# 1_P1.net
KiCad netlist of a schematic drawn in Altium Designer
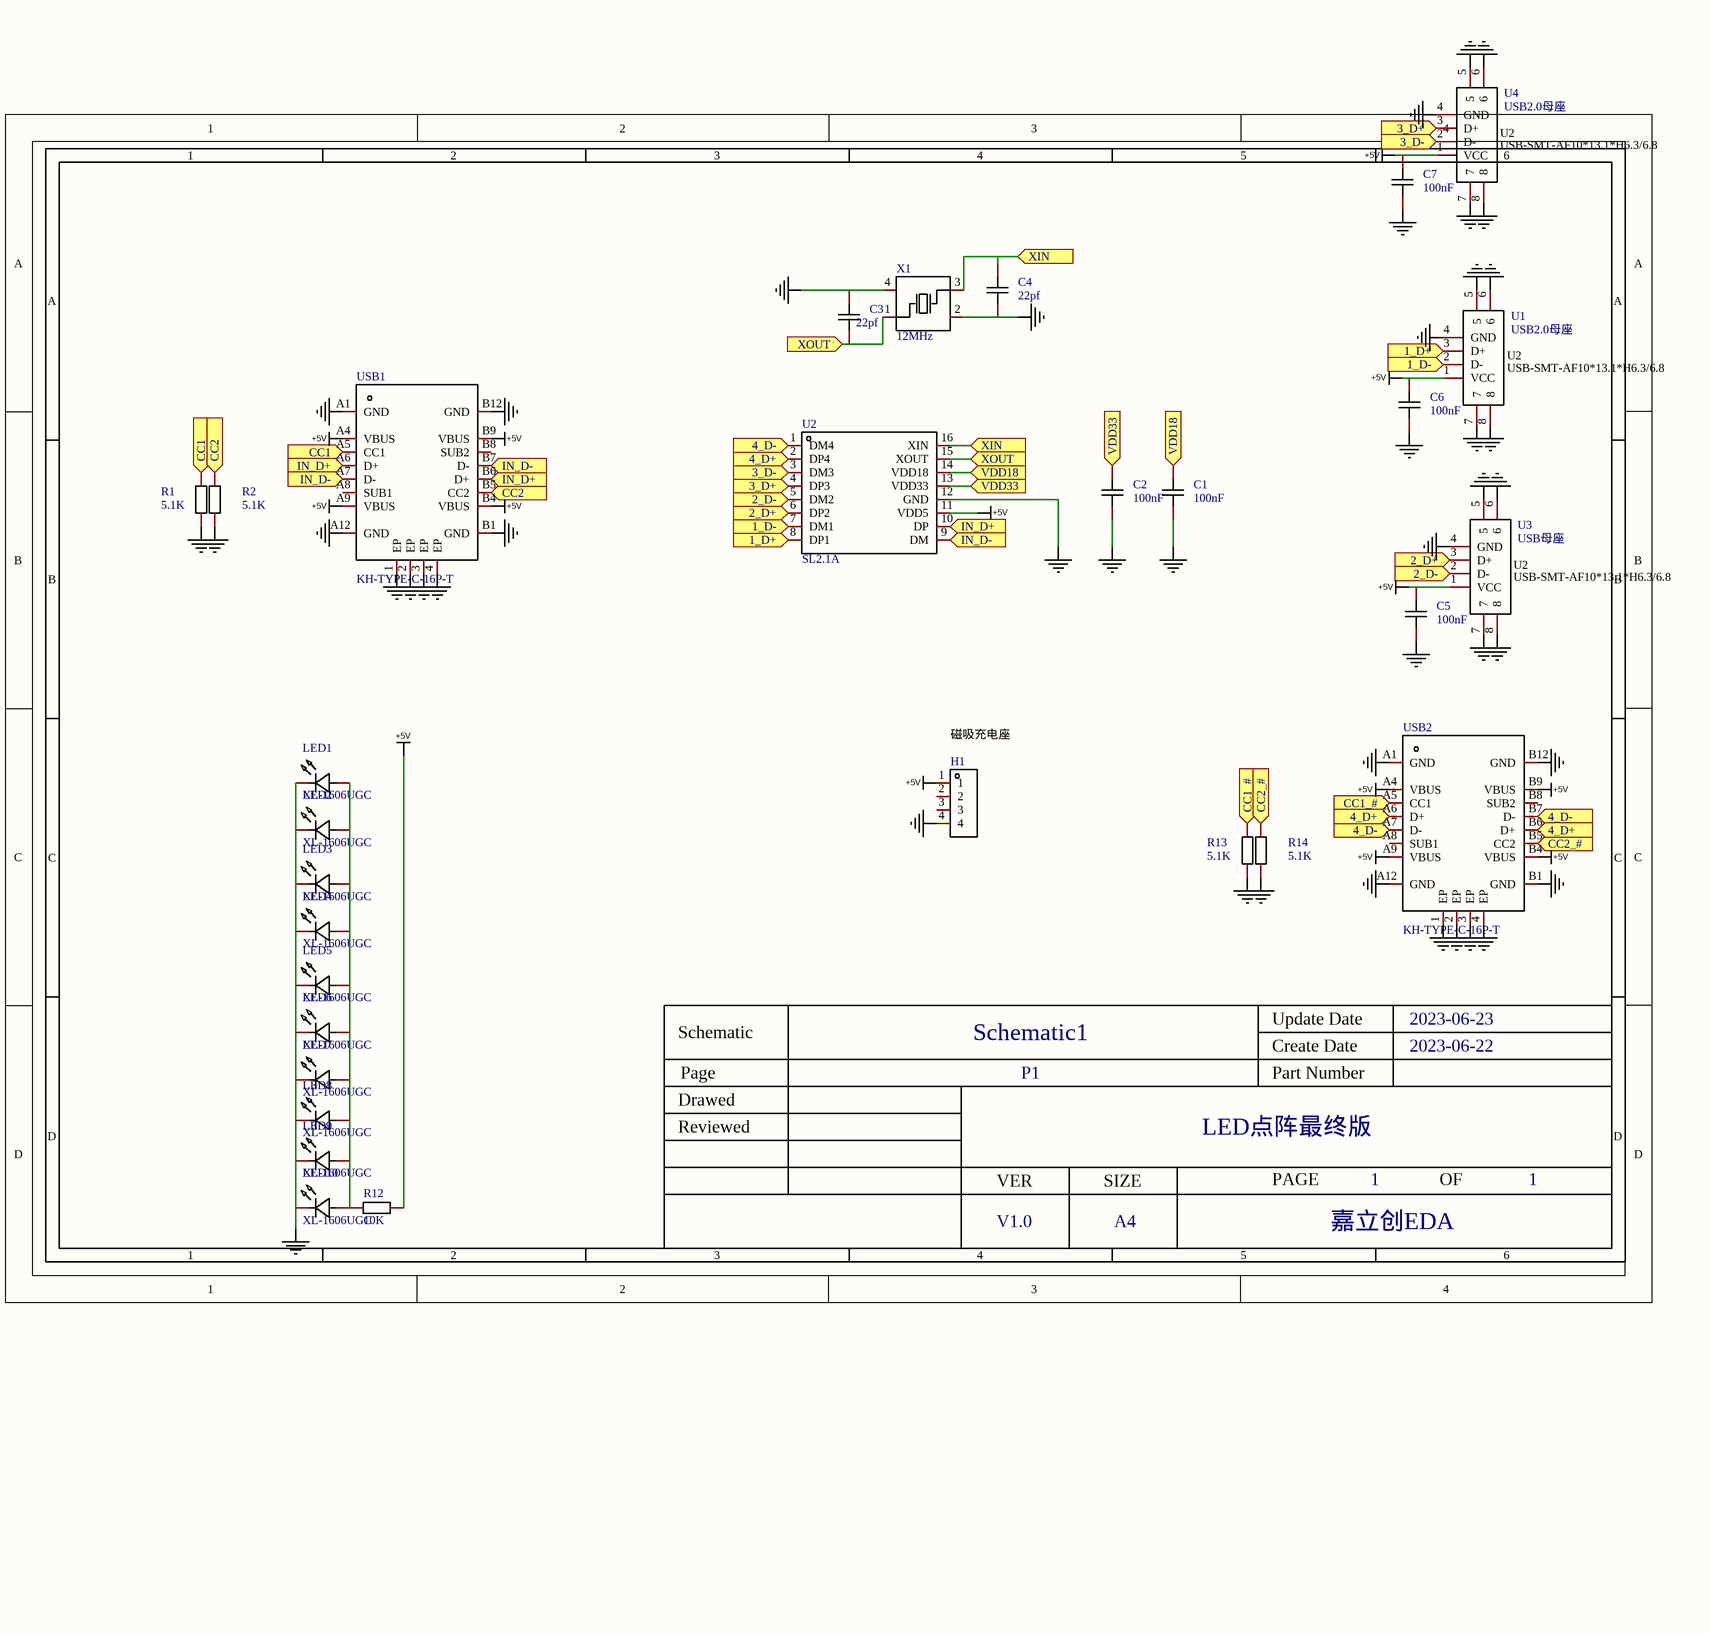
[diagram p0: 1_P1.schdoc]

(export (version "E")
  (design (tool "Eeschema 10.0.6"))
  (components
    (comp (ref "C1")
      (value "100nF")
      (fields (field (name "NAME") "100nF"))
      (libsource (lib "altium-import") (part "root_3_CAP_0603_"))
    )
    (comp (ref "C2")
      (value "100nF")
      (fields (field (name "NAME") "100nF"))
      (libsource (lib "altium-import") (part "root_3_CAP_0603_"))
    )
    (comp (ref "C3")
      (value "22pf")
      (fields (field (name "NAME") "22pf"))
      (libsource (lib "altium-import") (part "root_1_CAP_0603_"))
    )
    (comp (ref "C4")
      (value "22pf")
      (fields (field (name "NAME") "22pf"))
      (libsource (lib "altium-import") (part "root_1_CAP_0603_"))
    )
    (comp (ref "C5")
      (value "100nF")
      (fields (field (name "NAME") "100nF"))
      (libsource (lib "altium-import") (part "root_1_CAP_0603_"))
    )
    (comp (ref "C6")
      (value "100nF")
      (fields (field (name "NAME") "100nF"))
      (libsource (lib "altium-import") (part "root_1_CAP_0603_"))
    )
    (comp (ref "C7")
      (value "100nF")
      (fields (field (name "NAME") "100nF"))
      (libsource (lib "altium-import") (part "root_1_CAP_0603_"))
    )
    (comp (ref "H1")
      (value "HDR-M_2.54_1x4P")
      (libsource (lib "altium-import") (part "root_0_HDR-M_2.54_1x4P_"))
    )
    (comp (ref "LED1")
      (value "XL-1606UGC")
      (description "发光颜色:翠绿;主波长:520nm~530nm;色温:-;功率:80mW;安装方式:侧贴;")
      (fields (field (name "NAME") "XL-1606UGC") (field (name "MANUFACTURER") "XINGLIGHT(成兴光)"))
      (libsource (lib "altium-import") (part "root_0_XL-1606UGC_"))
    )
    (comp (ref "LED2")
      (value "XL-1606UGC")
      (description "发光颜色:翠绿;主波长:520nm~530nm;色温:-;功率:80mW;安装方式:侧贴;")
      (fields (field (name "NAME") "XL-1606UGC") (field (name "MANUFACTURER") "XINGLIGHT(成兴光)"))
      (libsource (lib "altium-import") (part "root_0_XL-1606UGC_"))
    )
    (comp (ref "LED3")
      (value "XL-1606UGC")
      (description "发光颜色:翠绿;主波长:520nm~530nm;色温:-;功率:80mW;安装方式:侧贴;")
      (fields (field (name "NAME") "XL-1606UGC") (field (name "MANUFACTURER") "XINGLIGHT(成兴光)"))
      (libsource (lib "altium-import") (part "root_0_XL-1606UGC_"))
    )
    (comp (ref "LED4")
      (value "XL-1606UGC")
      (description "发光颜色:翠绿;主波长:520nm~530nm;色温:-;功率:80mW;安装方式:侧贴;")
      (fields (field (name "NAME") "XL-1606UGC") (field (name "MANUFACTURER") "XINGLIGHT(成兴光)"))
      (libsource (lib "altium-import") (part "root_0_XL-1606UGC_"))
    )
    (comp (ref "LED5")
      (value "XL-1606UGC")
      (description "发光颜色:翠绿;主波长:520nm~530nm;色温:-;功率:80mW;安装方式:侧贴;")
      (fields (field (name "NAME") "XL-1606UGC") (field (name "MANUFACTURER") "XINGLIGHT(成兴光)"))
      (libsource (lib "altium-import") (part "root_0_XL-1606UGC_"))
    )
    (comp (ref "LED6")
      (value "XL-1606UGC")
      (description "发光颜色:翠绿;主波长:520nm~530nm;色温:-;功率:80mW;安装方式:侧贴;")
      (fields (field (name "NAME") "XL-1606UGC") (field (name "MANUFACTURER") "XINGLIGHT(成兴光)"))
      (libsource (lib "altium-import") (part "root_0_XL-1606UGC_"))
    )
    (comp (ref "LED7")
      (value "XL-1606UGC")
      (description "发光颜色:翠绿;主波长:520nm~530nm;色温:-;功率:80mW;安装方式:侧贴;")
      (fields (field (name "NAME") "XL-1606UGC") (field (name "MANUFACTURER") "XINGLIGHT(成兴光)"))
      (libsource (lib "altium-import") (part "root_0_XL-1606UGC_"))
    )
    (comp (ref "LED8")
      (value "XL-1606UGC")
      (description "发光颜色:翠绿;主波长:520nm~530nm;色温:-;功率:80mW;安装方式:侧贴;")
      (fields (field (name "NAME") "XL-1606UGC") (field (name "MANUFACTURER") "XINGLIGHT(成兴光)"))
      (libsource (lib "altium-import") (part "root_0_XL-1606UGC_"))
    )
    (comp (ref "LED9")
      (value "XL-1606UGC")
      (description "发光颜色:翠绿;主波长:520nm~530nm;色温:-;功率:80mW;安装方式:侧贴;")
      (fields (field (name "NAME") "XL-1606UGC") (field (name "MANUFACTURER") "XINGLIGHT(成兴光)"))
      (libsource (lib "altium-import") (part "root_0_XL-1606UGC_"))
    )
    (comp (ref "LED10")
      (value "XL-1606UGC")
      (description "发光颜色:翠绿;主波长:520nm~530nm;色温:-;功率:80mW;安装方式:侧贴;")
      (fields (field (name "NAME") "XL-1606UGC") (field (name "MANUFACTURER") "XINGLIGHT(成兴光)"))
      (libsource (lib "altium-import") (part "root_0_XL-1606UGC_"))
    )
    (comp (ref "R1")
      (value "5.1K")
      (fields (field (name "NAME") "5.1K"))
      (libsource (lib "altium-import") (part "root_1_Res_0603_"))
    )
    (comp (ref "R2")
      (value "5.1K")
      (fields (field (name "NAME") "5.1K"))
      (libsource (lib "altium-import") (part "root_1_Res_0603_"))
    )
    (comp (ref "R12")
      (value "10K")
      (fields (field (name "NAME") "10K"))
      (libsource (lib "altium-import") (part "root_0_Res_0603_"))
    )
    (comp (ref "R13")
      (value "5.1K")
      (fields (field (name "NAME") "5.1K"))
      (libsource (lib "altium-import") (part "root_1_Res_0603_"))
    )
    (comp (ref "R14")
      (value "5.1K")
      (fields (field (name "NAME") "5.1K"))
      (libsource (lib "altium-import") (part "root_1_Res_0603_"))
    )
    (comp (ref "U1")
      (value "USB-SMT-AF10.0-13.1*6.8/6.3")
      (fields (field (name "NAME") "USB2.0母座"))
      (libsource (lib "altium-import") (part "root_0_USB-SMT-AF10.0-13.1*6.8/6.3_"))
    )
    (comp (ref "U2")
      (value "SL2.1A")
      (description "应用功能:集线器;接口协议:-;")
      (fields (field (name "NAME") "SL2.1A") (field (name "MANUFACTURER") "CoreChips(和芯润德)"))
      (libsource (lib "altium-import") (part "root_0_SL2.1A_"))
    )
    (comp (ref "U3")
      (value "USB母座")
      (fields (field (name "NAME") "USB母座"))
      (libsource (lib "altium-import") (part "root_0_USB-SMT-AF10.0-13.1*6.8/6.3_"))
    )
    (comp (ref "U4")
      (value "USB-SMT-AF10.0-13.1*6.8/6.3")
      (fields (field (name "NAME") "USB2.0母座"))
      (libsource (lib "altium-import") (part "root_0_USB-SMT-AF10.0-13.1*6.8/6.3_"))
    )
    (comp (ref "USB1")
      (value "KH-TYPE-C-16P-T")
      (description "连接器类型:Type-C;标准:-;公母:母座;触点数量:16;端口数量:1;安装方式:卧贴;额定电流 - 电源:500mA;工作温度范围:-30℃~+80℃;")
      (fields (field (name "NAME") "KH-TYPE-C-16P-T") (field (name "MANUFACTURER") "kinghelm(金航标)"))
      (libsource (lib "altium-import") (part "root_0_KH-TYPE-C-16P-T_"))
    )
    (comp (ref "USB2")
      (value "KH-TYPE-C-16P-T")
      (description "连接器类型:Type-C;标准:-;公母:母座;触点数量:16;端口数量:1;安装方式:卧贴;额定电流 - 电源:500mA;工作温度范围:-30℃~+80℃;")
      (fields (field (name "NAME") "KH-TYPE-C-16P-T") (field (name "MANUFACTURER") "kinghelm(金航标)"))
      (libsource (lib "altium-import") (part "root_0_KH-TYPE-C-16P-T_"))
    )
    (comp (ref "X1")
      (value "12MHz")
      (description "频率:12MHz;频率公差:±10ppm;负载电容:20pF;")
      (fields
        (field (name "NAME") "12MHz")
        (field (name "MANUFACTURER") "YXC(扬兴晶振)")
        (field (name "MANUFACTURER PART") "X322512MSB4SI")
      )
      (libsource (lib "altium-import") (part "root_0_X322512MSB4SI_"))
    )
  )
  (nets
    (net (code "1") (name "+5V") (class "Default")
      (node (ref "C5") (pin "2") (pinfunction "2_2") (pintype "passive"))
      (node (ref "C6") (pin "2") (pinfunction "2_2") (pintype "passive"))
      (node (ref "C7") (pin "2") (pinfunction "2_2") (pintype "passive"))
      (node (ref "H1") (pin "1") (pinfunction "1_1") (pintype "passive"))
      (node (ref "R12") (pin "2") (pinfunction "2_2") (pintype "passive"))
      (node (ref "U1") (pin "1") (pinfunction "VCC_1") (pintype "passive"))
      (node (ref "U2") (pin "11") (pinfunction "VDD5_11") (pintype "passive"))
      (node (ref "U3") (pin "1") (pinfunction "VCC_1") (pintype "passive"))
      (node (ref "U4") (pin "1") (pinfunction "VCC_1") (pintype "passive"))
      (node (ref "USB1") (pin "A4") (pinfunction "VBUS_A4") (pintype "passive"))
      (node (ref "USB1") (pin "A9") (pinfunction "VBUS_A9") (pintype "passive"))
      (node (ref "USB1") (pin "B4") (pinfunction "VBUS_B4") (pintype "passive"))
      (node (ref "USB1") (pin "B9") (pinfunction "VBUS_B9") (pintype "passive"))
      (node (ref "USB2") (pin "A4") (pinfunction "VBUS_A4") (pintype "passive"))
      (node (ref "USB2") (pin "A9") (pinfunction "VBUS_A9") (pintype "passive"))
      (node (ref "USB2") (pin "B4") (pinfunction "VBUS_B4") (pintype "passive"))
      (node (ref "USB2") (pin "B9") (pinfunction "VBUS_B9") (pintype "passive"))
    )
    (net (code "2") (name "/1_D+") (class "Default")
      (node (ref "U1") (pin "3") (pinfunction "D+_3") (pintype "passive"))
      (node (ref "U2") (pin "8") (pinfunction "DP1_8") (pintype "passive"))
    )
    (net (code "3") (name "/1_D-") (class "Default")
      (node (ref "U1") (pin "2") (pinfunction "D-_2") (pintype "passive"))
      (node (ref "U2") (pin "7") (pinfunction "DM1_7") (pintype "passive"))
    )
    (net (code "4") (name "/2_D+") (class "Default")
      (node (ref "U2") (pin "6") (pinfunction "DP2_6") (pintype "passive"))
      (node (ref "U3") (pin "3") (pinfunction "D+_3") (pintype "passive"))
    )
    (net (code "5") (name "/2_D-") (class "Default")
      (node (ref "U2") (pin "5") (pinfunction "DM2_5") (pintype "passive"))
      (node (ref "U3") (pin "2") (pinfunction "D-_2") (pintype "passive"))
    )
    (net (code "6") (name "/3_D+") (class "Default")
      (node (ref "U2") (pin "4") (pinfunction "DP3_4") (pintype "passive"))
      (node (ref "U4") (pin "3") (pinfunction "D+_3") (pintype "passive"))
    )
    (net (code "7") (name "/3_D-") (class "Default")
      (node (ref "U2") (pin "3") (pinfunction "DM3_3") (pintype "passive"))
      (node (ref "U4") (pin "2") (pinfunction "D-_2") (pintype "passive"))
    )
    (net (code "8") (name "/4_D+") (class "Default")
      (node (ref "U2") (pin "2") (pinfunction "DP4_2") (pintype "passive"))
      (node (ref "USB2") (pin "A6") (pinfunction "D+_A6") (pintype "passive"))
      (node (ref "USB2") (pin "B6") (pinfunction "D+_B6") (pintype "passive"))
    )
    (net (code "9") (name "/4_D-") (class "Default")
      (node (ref "U2") (pin "1") (pinfunction "DM4_1") (pintype "passive"))
      (node (ref "USB2") (pin "A7") (pinfunction "D-_A7") (pintype "passive"))
      (node (ref "USB2") (pin "B7") (pinfunction "D-_B7") (pintype "passive"))
    )
    (net (code "10") (name "/CC1") (class "Default")
      (node (ref "R1") (pin "2") (pinfunction "2_2") (pintype "passive"))
      (node (ref "USB1") (pin "A5") (pinfunction "CC1_A5") (pintype "passive"))
    )
    (net (code "11") (name "/CC1_#") (class "Default")
      (node (ref "R13") (pin "2") (pinfunction "2_2") (pintype "passive"))
      (node (ref "USB2") (pin "A5") (pinfunction "CC1_A5") (pintype "passive"))
    )
    (net (code "12") (name "/CC2") (class "Default")
      (node (ref "R2") (pin "2") (pinfunction "2_2") (pintype "passive"))
      (node (ref "USB1") (pin "B5") (pinfunction "CC2_B5") (pintype "passive"))
    )
    (net (code "13") (name "/CC2_#") (class "Default")
      (node (ref "R14") (pin "2") (pinfunction "2_2") (pintype "passive"))
      (node (ref "USB2") (pin "B5") (pinfunction "CC2_B5") (pintype "passive"))
    )
    (net (code "14") (name "/IN_D+") (class "Default")
      (node (ref "U2") (pin "10") (pinfunction "DP_10") (pintype "passive"))
      (node (ref "USB1") (pin "A6") (pinfunction "D+_A6") (pintype "passive"))
      (node (ref "USB1") (pin "B6") (pinfunction "D+_B6") (pintype "passive"))
    )
    (net (code "15") (name "/IN_D-") (class "Default")
      (node (ref "U2") (pin "9") (pinfunction "DM_9") (pintype "passive"))
      (node (ref "USB1") (pin "A7") (pinfunction "D-_A7") (pintype "passive"))
      (node (ref "USB1") (pin "B7") (pinfunction "D-_B7") (pintype "passive"))
    )
    (net (code "16") (name "/VDD18") (class "Default")
      (node (ref "C1") (pin "1") (pinfunction "1_1") (pintype "passive"))
      (node (ref "U2") (pin "14") (pinfunction "VDD18_14") (pintype "passive"))
    )
    (net (code "17") (name "/VDD33") (class "Default")
      (node (ref "C2") (pin "1") (pinfunction "1_1") (pintype "passive"))
      (node (ref "U2") (pin "13") (pinfunction "VDD33_13") (pintype "passive"))
    )
    (net (code "18") (name "/XIN") (class "Default")
      (node (ref "C4") (pin "2") (pinfunction "2_2") (pintype "passive"))
      (node (ref "U2") (pin "16") (pinfunction "XIN_16") (pintype "passive"))
      (node (ref "X1") (pin "3") (pinfunction "OSC2_3") (pintype "passive"))
    )
    (net (code "19") (name "/XOUT") (class "Default")
      (node (ref "C3") (pin "1") (pinfunction "1_1") (pintype "passive"))
      (node (ref "U2") (pin "15") (pinfunction "XOUT_15") (pintype "passive"))
      (node (ref "X1") (pin "1") (pinfunction "OSC1_1") (pintype "passive"))
    )
    (net (code "20") (name "<NO NET>") (class "Default")
      (node (ref "C1") (pin "2") (pinfunction "2_2") (pintype "passive"))
      (node (ref "C2") (pin "2") (pinfunction "2_2") (pintype "passive"))
      (node (ref "C3") (pin "2") (pinfunction "2_2") (pintype "passive"))
      (node (ref "C4") (pin "1") (pinfunction "1_1") (pintype "passive"))
      (node (ref "C5") (pin "1") (pinfunction "1_1") (pintype "passive"))
      (node (ref "C6") (pin "1") (pinfunction "1_1") (pintype "passive"))
      (node (ref "C7") (pin "1") (pinfunction "1_1") (pintype "passive"))
      (node (ref "H1") (pin "4") (pinfunction "4_4") (pintype "passive"))
      (node (ref "LED1") (pin "2") (pinfunction "K_2") (pintype "passive"))
      (node (ref "LED10") (pin "2") (pinfunction "K_2") (pintype "passive"))
      (node (ref "LED2") (pin "2") (pinfunction "K_2") (pintype "passive"))
      (node (ref "LED3") (pin "2") (pinfunction "K_2") (pintype "passive"))
      (node (ref "LED4") (pin "2") (pinfunction "K_2") (pintype "passive"))
      (node (ref "LED5") (pin "2") (pinfunction "K_2") (pintype "passive"))
      (node (ref "LED6") (pin "2") (pinfunction "K_2") (pintype "passive"))
      (node (ref "LED7") (pin "2") (pinfunction "K_2") (pintype "passive"))
      (node (ref "LED8") (pin "2") (pinfunction "K_2") (pintype "passive"))
      (node (ref "LED9") (pin "2") (pinfunction "K_2") (pintype "passive"))
      (node (ref "R1") (pin "1") (pinfunction "1_1") (pintype "passive"))
      (node (ref "R13") (pin "1") (pinfunction "1_1") (pintype "passive"))
      (node (ref "R14") (pin "1") (pinfunction "1_1") (pintype "passive"))
      (node (ref "R2") (pin "1") (pinfunction "1_1") (pintype "passive"))
      (node (ref "U1") (pin "4") (pinfunction "GND_4") (pintype "passive"))
      (node (ref "U1") (pin "5") (pinfunction "5_5") (pintype "passive"))
      (node (ref "U1") (pin "6") (pinfunction "6_6") (pintype "passive"))
      (node (ref "U1") (pin "7") (pinfunction "7_7") (pintype "passive"))
      (node (ref "U1") (pin "8") (pinfunction "8_8") (pintype "passive"))
      (node (ref "U2") (pin "12") (pinfunction "GND_12") (pintype "passive"))
      (node (ref "U3") (pin "4") (pinfunction "GND_4") (pintype "passive"))
      (node (ref "U3") (pin "5") (pinfunction "5_5") (pintype "passive"))
      (node (ref "U3") (pin "6") (pinfunction "6_6") (pintype "passive"))
      (node (ref "U3") (pin "7") (pinfunction "7_7") (pintype "passive"))
      (node (ref "U3") (pin "8") (pinfunction "8_8") (pintype "passive"))
      (node (ref "U4") (pin "4") (pinfunction "GND_4") (pintype "passive"))
      (node (ref "U4") (pin "5") (pinfunction "5_5") (pintype "passive"))
      (node (ref "U4") (pin "6") (pinfunction "6_6") (pintype "passive"))
      (node (ref "U4") (pin "7") (pinfunction "7_7") (pintype "passive"))
      (node (ref "U4") (pin "8") (pinfunction "8_8") (pintype "passive"))
      (node (ref "USB1") (pin "1") (pinfunction "EP_1") (pintype "passive"))
      (node (ref "USB1") (pin "2") (pinfunction "EP_2") (pintype "passive"))
      (node (ref "USB1") (pin "3") (pinfunction "EP_3") (pintype "passive"))
      (node (ref "USB1") (pin "4") (pinfunction "EP_4") (pintype "passive"))
      (node (ref "USB1") (pin "A1") (pinfunction "GND_A1") (pintype "passive"))
      (node (ref "USB1") (pin "A12") (pinfunction "GND_A12") (pintype "passive"))
      (node (ref "USB1") (pin "B1") (pinfunction "GND_B1") (pintype "passive"))
      (node (ref "USB1") (pin "B12") (pinfunction "GND_B12") (pintype "passive"))
      (node (ref "USB2") (pin "1") (pinfunction "EP_1") (pintype "passive"))
      (node (ref "USB2") (pin "2") (pinfunction "EP_2") (pintype "passive"))
      (node (ref "USB2") (pin "3") (pinfunction "EP_3") (pintype "passive"))
      (node (ref "USB2") (pin "4") (pinfunction "EP_4") (pintype "passive"))
      (node (ref "USB2") (pin "A1") (pinfunction "GND_A1") (pintype "passive"))
      (node (ref "USB2") (pin "A12") (pinfunction "GND_A12") (pintype "passive"))
      (node (ref "USB2") (pin "B1") (pinfunction "GND_B1") (pintype "passive"))
      (node (ref "USB2") (pin "B12") (pinfunction "GND_B12") (pintype "passive"))
      (node (ref "X1") (pin "2") (pinfunction "GND_2") (pintype "passive"))
      (node (ref "X1") (pin "4") (pinfunction "GND_4") (pintype "passive"))
    )
    (net (code "21") (name "Net-(LED1-A)") (class "Default")
      (node (ref "LED1") (pin "1") (pinfunction "A_1") (pintype "passive"))
      (node (ref "LED10") (pin "1") (pinfunction "A_1") (pintype "passive"))
      (node (ref "LED2") (pin "1") (pinfunction "A_1") (pintype "passive"))
      (node (ref "LED3") (pin "1") (pinfunction "A_1") (pintype "passive"))
      (node (ref "LED4") (pin "1") (pinfunction "A_1") (pintype "passive"))
      (node (ref "LED5") (pin "1") (pinfunction "A_1") (pintype "passive"))
      (node (ref "LED6") (pin "1") (pinfunction "A_1") (pintype "passive"))
      (node (ref "LED7") (pin "1") (pinfunction "A_1") (pintype "passive"))
      (node (ref "LED8") (pin "1") (pinfunction "A_1") (pintype "passive"))
      (node (ref "LED9") (pin "1") (pinfunction "A_1") (pintype "passive"))
      (node (ref "R12") (pin "1") (pinfunction "1_1") (pintype "passive"))
    )
    (net (code "22") (name "unconnected-(H1-Pad2)") (class "Default")
      (node (ref "H1") (pin "2") (pinfunction "2_2") (pintype "passive"))
    )
    (net (code "23") (name "unconnected-(H1-Pad3)") (class "Default")
      (node (ref "H1") (pin "3") (pinfunction "3_3") (pintype "passive"))
    )
    (net (code "24") (name "unconnected-(USB1-SUB1-PadA8)") (class "Default")
      (node (ref "USB1") (pin "A8") (pinfunction "SUB1_A8") (pintype "passive"))
    )
    (net (code "25") (name "unconnected-(USB1-SUB2-PadB8)") (class "Default")
      (node (ref "USB1") (pin "B8") (pinfunction "SUB2_B8") (pintype "passive"))
    )
    (net (code "26") (name "unconnected-(USB2-SUB1-PadA8)") (class "Default")
      (node (ref "USB2") (pin "A8") (pinfunction "SUB1_A8") (pintype "passive"))
    )
    (net (code "27") (name "unconnected-(USB2-SUB2-PadB8)") (class "Default")
      (node (ref "USB2") (pin "B8") (pinfunction "SUB2_B8") (pintype "passive"))
    )
  )
)
